# pot-board.net
KiCad netlist of a schematic drawn in EAGLE
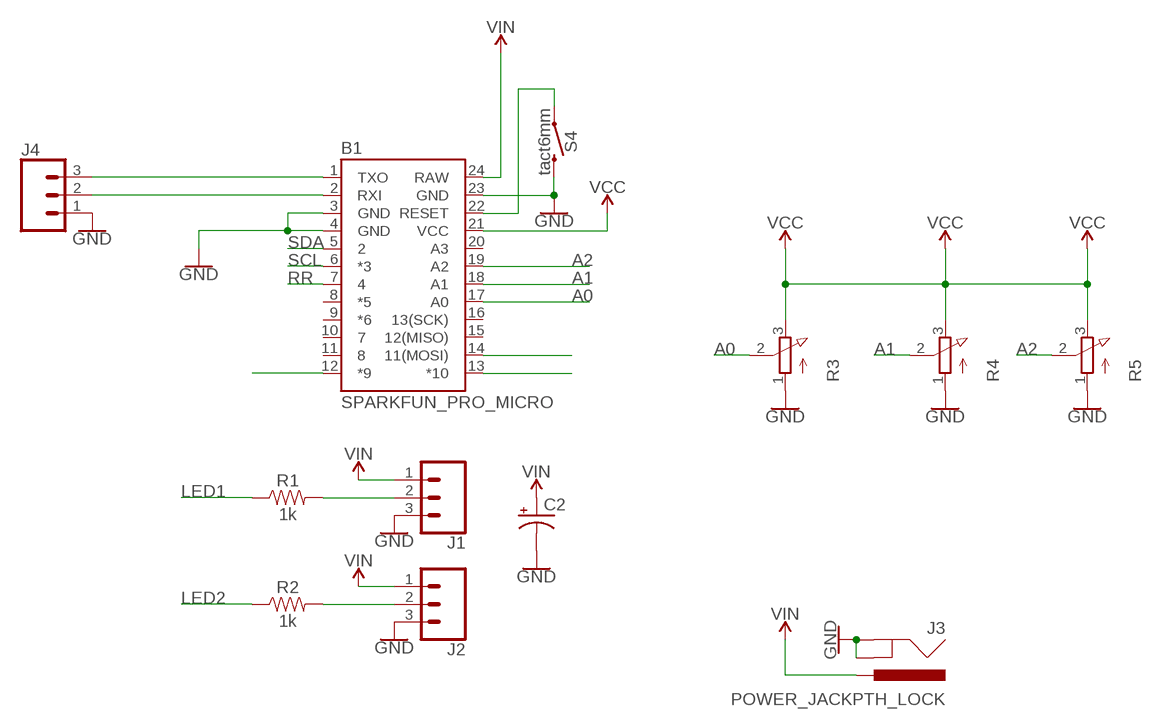
[diagram p0: schematic, sheet 1]

(export (version "E")
  (design (tool "Eeschema 10.0.6"))
  (components
    (comp (ref "B1")
      (value "SPARKFUN_PRO_MICRO")
      (footprint "eagle-import:SPARKFUN_PRO_MICRO")
      (libsource (lib "eagle-import") (part "SPARKFUN_PRO_MICRO"))
    )
    (comp (ref "C2")
      (value "CPOL-USE3.5-8")
      (footprint "eagle-import:E3,5-8")
      (libsource (lib "eagle-import") (part "CPOL-USE3.5-8"))
    )
    (comp (ref "J1")
      (value "CONN_03")
      (footprint "eagle-import:1X03")
      (libsource (lib "eagle-import") (part "CONN_03"))
    )
    (comp (ref "J2")
      (value "CONN_03")
      (footprint "eagle-import:1X03")
      (libsource (lib "eagle-import") (part "CONN_03"))
    )
    (comp (ref "J3")
      (value "POWER_JACKPTH_LOCK")
      (footprint "eagle-import:POWER_JACK_PTH_LOCK")
      (libsource (lib "eagle-import") (part "POWER_JACKPTH_LOCK"))
    )
    (comp (ref "J4")
      (value "CONN_03")
      (footprint "eagle-import:1X03")
      (libsource (lib "eagle-import") (part "CONN_03"))
    )
    (comp (ref "R1")
      (value "1k")
      (footprint "eagle-import:AXIAL-0.3")
      (libsource (lib "eagle-import") (part "1KOHM-HORIZ-1/4W-5%"))
    )
    (comp (ref "R2")
      (value "1k")
      (footprint "eagle-import:AXIAL-0.3")
      (libsource (lib "eagle-import") (part "1KOHM-HORIZ-1/4W-5%"))
    )
    (comp (ref "R3")
      (value "3RP/1610N")
      (footprint "eagle-import:3RP_1610N")
      (libsource (lib "eagle-import") (part "3RP/1610N"))
    )
    (comp (ref "R4")
      (value "3RP/1610N")
      (footprint "eagle-import:3RP_1610N")
      (libsource (lib "eagle-import") (part "3RP/1610N"))
    )
    (comp (ref "R5")
      (value "3RP/1610N")
      (footprint "eagle-import:3RP_1610N")
      (libsource (lib "eagle-import") (part "3RP/1610N"))
    )
    (comp (ref "S4")
      (value "tact6mm")
      (footprint "eagle-import:TACTILE_SWITCH_PTH_6.0MM")
      (libsource (lib "eagle-import") (part "MOMENTARY-SWITCH-SPST-PTH-6.0MM"))
    )
  )
  (nets
    (net (code "1") (name "/A0") (class "Default")
      (node (ref "B1") (pin "17") (pinfunction "A0_17") (pintype "bidirectional"))
      (node (ref "R3") (pin "2") (pinfunction "S_2") (pintype "passive"))
    )
    (net (code "2") (name "/A1") (class "Default")
      (node (ref "B1") (pin "18") (pinfunction "A1_18") (pintype "bidirectional"))
      (node (ref "R4") (pin "2") (pinfunction "S_2") (pintype "passive"))
    )
    (net (code "3") (name "/A2") (class "Default")
      (node (ref "B1") (pin "19") (pinfunction "A2_19") (pintype "bidirectional"))
      (node (ref "R5") (pin "2") (pinfunction "S_2") (pintype "passive"))
    )
    (net (code "4") (name "/LED1") (class "Default")
      (node (ref "B1") (pin "13") (pinfunction "*10_13") (pintype "bidirectional"))
      (node (ref "R1") (pin "P$1") (pinfunction "1_P$1") (pintype "passive"))
    )
    (net (code "5") (name "/LED2") (class "Default")
      (node (ref "B1") (pin "14") (pinfunction "11(MOSI)_14") (pintype "bidirectional"))
      (node (ref "R2") (pin "P$1") (pinfunction "1_P$1") (pintype "passive"))
    )
    (net (code "6") (name "/RR") (class "Default")
      (node (ref "B1") (pin "7") (pinfunction "4_7") (pintype "bidirectional"))
    )
    (net (code "7") (name "/SCL") (class "Default")
      (node (ref "B1") (pin "6") (pinfunction "*3_6") (pintype "bidirectional"))
    )
    (net (code "8") (name "/SDA") (class "Default")
      (node (ref "B1") (pin "5") (pinfunction "2_5") (pintype "bidirectional"))
    )
    (net (code "9") (name "GND") (class "Default")
      (node (ref "B1") (pin "23") (pinfunction "GND_23") (pintype "power_in"))
      (node (ref "B1") (pin "3") (pinfunction "GND_3") (pintype "power_in"))
      (node (ref "B1") (pin "4") (pinfunction "GND_4") (pintype "power_in"))
      (node (ref "C2") (pin "-") (pinfunction "-_-") (pintype "passive"))
      (node (ref "J1") (pin "3") (pinfunction "3_3") (pintype "passive"))
      (node (ref "J2") (pin "3") (pinfunction "3_3") (pintype "passive"))
      (node (ref "J3") (pin "GND") (pinfunction "GND_GND") (pintype "bidirectional"))
      (node (ref "J3") (pin "GNDBREAK") (pinfunction "GNDBREAK_GNDBREAK") (pintype "bidirectional"))
      (node (ref "J4") (pin "1") (pinfunction "1_1") (pintype "passive"))
      (node (ref "R3") (pin "1") (pinfunction "A_1") (pintype "passive"))
      (node (ref "R4") (pin "1") (pinfunction "A_1") (pintype "passive"))
      (node (ref "R5") (pin "1") (pinfunction "A_1") (pintype "passive"))
      (node (ref "S4") (pin "3") (pinfunction "2_3") (pintype "passive"))
    )
    (net (code "10") (name "Net-(B1-RESET)") (class "Default")
      (node (ref "B1") (pin "22") (pinfunction "RESET_22") (pintype "bidirectional"))
      (node (ref "S4") (pin "1") (pinfunction "1_1") (pintype "passive"))
    )
    (net (code "11") (name "Net-(B1-RXI)") (class "Default")
      (node (ref "B1") (pin "2") (pinfunction "RXI_2") (pintype "bidirectional"))
      (node (ref "J4") (pin "2") (pinfunction "2_2") (pintype "passive"))
    )
    (net (code "12") (name "Net-(B1-TXO)") (class "Default")
      (node (ref "B1") (pin "1") (pinfunction "TXO_1") (pintype "bidirectional"))
      (node (ref "J4") (pin "3") (pinfunction "3_3") (pintype "passive"))
    )
    (net (code "13") (name "Net-(R1-2)") (class "Default")
      (node (ref "J1") (pin "2") (pinfunction "2_2") (pintype "passive"))
      (node (ref "R1") (pin "P$2") (pinfunction "2_P$2") (pintype "passive"))
    )
    (net (code "14") (name "Net-(R2-2)") (class "Default")
      (node (ref "J2") (pin "2") (pinfunction "2_2") (pintype "passive"))
      (node (ref "R2") (pin "P$2") (pinfunction "2_P$2") (pintype "passive"))
    )
    (net (code "15") (name "VCC") (class "Default")
      (node (ref "B1") (pin "21") (pinfunction "VCC_21") (pintype "power_in"))
      (node (ref "R3") (pin "3") (pinfunction "E_3") (pintype "passive"))
      (node (ref "R4") (pin "3") (pinfunction "E_3") (pintype "passive"))
      (node (ref "R5") (pin "3") (pinfunction "E_3") (pintype "passive"))
    )
    (net (code "16") (name "VIN") (class "Default")
      (node (ref "B1") (pin "24") (pinfunction "RAW_24") (pintype "power_in"))
      (node (ref "C2") (pin "+") (pinfunction "+_+") (pintype "passive"))
      (node (ref "J1") (pin "1") (pinfunction "1_1") (pintype "passive"))
      (node (ref "J2") (pin "1") (pinfunction "1_1") (pintype "passive"))
      (node (ref "J3") (pin "PWR") (pinfunction "PWR_PWR") (pintype "bidirectional"))
    )
    (net (code "17") (name "unconnected-(B1-*5-Pad8)") (class "Default")
      (node (ref "B1") (pin "8") (pinfunction "*5_8") (pintype "bidirectional"))
    )
    (net (code "18") (name "unconnected-(B1-*6-Pad9)") (class "Default")
      (node (ref "B1") (pin "9") (pinfunction "*6_9") (pintype "bidirectional"))
    )
    (net (code "19") (name "unconnected-(B1-*9-Pad12)") (class "Default")
      (node (ref "B1") (pin "12") (pinfunction "*9_12") (pintype "bidirectional"))
    )
    (net (code "20") (name "unconnected-(B1-7-Pad10)") (class "Default")
      (node (ref "B1") (pin "10") (pinfunction "7_10") (pintype "bidirectional"))
    )
    (net (code "21") (name "unconnected-(B1-8-Pad11)") (class "Default")
      (node (ref "B1") (pin "11") (pinfunction "8_11") (pintype "bidirectional"))
    )
    (net (code "22") (name "unconnected-(B1-12(MISO)-Pad15)") (class "Default")
      (node (ref "B1") (pin "15") (pinfunction "12(MISO)_15") (pintype "bidirectional"))
    )
    (net (code "23") (name "unconnected-(B1-13(SCK)-Pad16)") (class "Default")
      (node (ref "B1") (pin "16") (pinfunction "13(SCK)_16") (pintype "bidirectional"))
    )
    (net (code "24") (name "unconnected-(B1-A3-Pad20)") (class "Default")
      (node (ref "B1") (pin "20") (pinfunction "A3_20") (pintype "bidirectional"))
    )
  )
)
